# USB2BT.net
KiCad netlist of a schematic drawn in Altium Designer
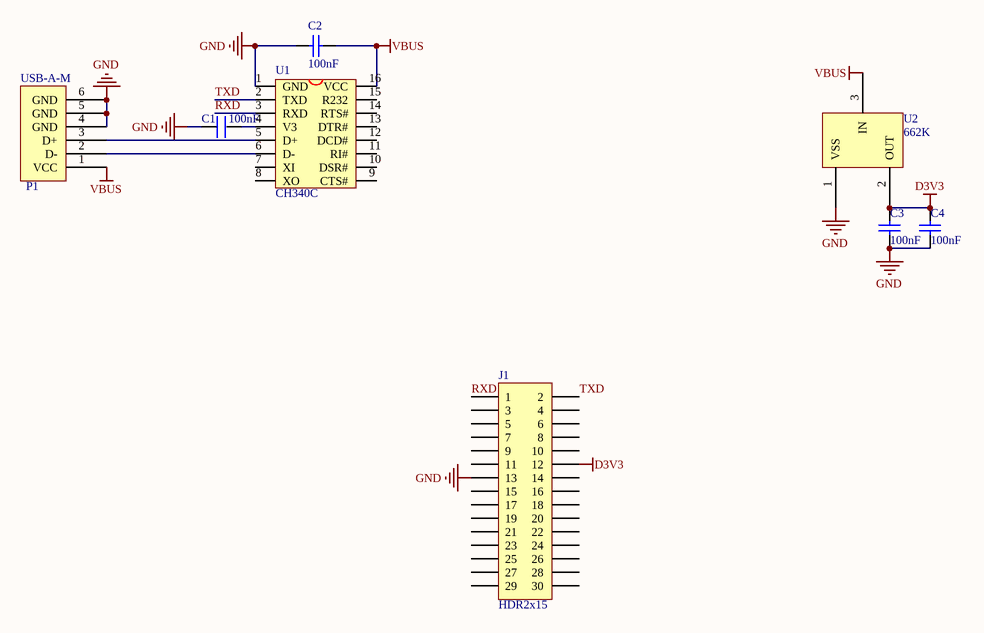
[diagram p0: USB2BT.SchDoc]

(export (version "E")
  (design (tool "Eeschema 10.0.6"))
  (components
    (comp (ref "C1")
      (value "100nF")
      (footprint "0603C")
      (libsource (lib "WarShip V3 STM32103封装库") (part "C"))
    )
    (comp (ref "C2")
      (value "100nF")
      (footprint "0603C")
      (description "Capacitor")
      (fields (field (name "PUBLISHER") "Altium Limited"))
      (libsource (lib "Crazy_PCB") (part "Cap"))
    )
    (comp (ref "C3")
      (value "100nF")
      (footprint "0603C")
      (description "Capacitor")
      (fields (field (name "PUBLISHER") "Altium Limited"))
      (libsource (lib "Crazy_PCB") (part "Cap"))
    )
    (comp (ref "C4")
      (value "100nF")
      (footprint "0603C")
      (description "Capacitor")
      (fields (field (name "PUBLISHER") "Altium Limited"))
      (libsource (lib "Crazy_PCB") (part "Cap"))
    )
    (comp (ref "J1")
      (value "HDR2x15")
      (footprint "HC-05/06/08V15")
      (description "Connector")
      (libsource (lib "General") (part "HDR2x15"))
    )
    (comp (ref "P1") (value "USB-A-M") (footprint "USB-A-M") (libsource (lib "DX") (part "USB-B")))
    (comp (ref "U1")
      (value "CH340C")
      (footprint "SO-16")
      (description "USB2UART")
      (libsource (lib "WarShip V3 STM32103封装库") (part "CH340G"))
    )
    (comp (ref "U2") (value "662K") (footprint "SOT-23") (libsource (lib "SS") (part "662K")))
  )
  (nets
    (net (code "1") (name "/RXD") (class "Default")
      (node (ref "J1") (pin "1") (pinfunction "1_1") (pintype "passive"))
      (node (ref "U1") (pin "3") (pinfunction "RXD_3") (pintype "passive"))
    )
    (net (code "2") (name "/TXD") (class "Default")
      (node (ref "J1") (pin "2") (pinfunction "2_2") (pintype "passive"))
      (node (ref "U1") (pin "2") (pinfunction "TXD_2") (pintype "passive"))
    )
    (net (code "3") (name "D3V3") (class "Default")
      (node (ref "C3") (pin "2") (pinfunction "2_2") (pintype "passive"))
      (node (ref "C4") (pin "2") (pinfunction "2_2") (pintype "passive"))
      (node (ref "J1") (pin "12") (pinfunction "12_12") (pintype "passive"))
      (node (ref "U2") (pin "2") (pinfunction "OUT_2") (pintype "passive"))
    )
    (net (code "4") (name "GND") (class "Default")
      (node (ref "C1") (pin "1") (pintype "passive"))
      (node (ref "C2") (pin "1") (pinfunction "1_1") (pintype "passive"))
      (node (ref "C3") (pin "1") (pinfunction "1_1") (pintype "passive"))
      (node (ref "C4") (pin "1") (pinfunction "1_1") (pintype "passive"))
      (node (ref "J1") (pin "13") (pinfunction "13_13") (pintype "passive"))
      (node (ref "P1") (pin "4") (pinfunction "GND_4") (pintype "passive"))
      (node (ref "P1") (pin "5") (pinfunction "GND_5") (pintype "passive"))
      (node (ref "P1") (pin "6") (pinfunction "GND_6") (pintype "passive"))
      (node (ref "U1") (pin "1") (pinfunction "GND_1") (pintype "passive"))
      (node (ref "U2") (pin "1") (pinfunction "VSS_1") (pintype "passive"))
    )
    (net (code "5") (name "Net-(P1-D+)") (class "Default")
      (node (ref "P1") (pin "3") (pinfunction "D+_3") (pintype "passive"))
      (node (ref "U1") (pin "5") (pinfunction "D+_5") (pintype "passive"))
    )
    (net (code "6") (name "Net-(P1-D-)") (class "Default")
      (node (ref "P1") (pin "2") (pinfunction "D-_2") (pintype "passive"))
      (node (ref "U1") (pin "6") (pinfunction "D-_6") (pintype "passive"))
    )
    (net (code "7") (name "Net-(U1-V3)") (class "Default")
      (node (ref "C1") (pin "2") (pintype "passive"))
      (node (ref "U1") (pin "4") (pinfunction "V3_4") (pintype "passive"))
    )
    (net (code "8") (name "VBUS") (class "Default")
      (node (ref "C2") (pin "2") (pinfunction "2_2") (pintype "passive"))
      (node (ref "P1") (pin "1") (pinfunction "VCC_1") (pintype "passive"))
      (node (ref "U1") (pin "16") (pinfunction "VCC_16") (pintype "passive"))
      (node (ref "U2") (pin "3") (pinfunction "IN_3") (pintype "passive"))
    )
    (net (code "9") (name "unconnected-(J1-Pad3)") (class "Default")
      (node (ref "J1") (pin "3") (pinfunction "3_3") (pintype "passive"))
    )
    (net (code "10") (name "unconnected-(J1-Pad4)") (class "Default")
      (node (ref "J1") (pin "4") (pinfunction "4_4") (pintype "passive"))
    )
    (net (code "11") (name "unconnected-(J1-Pad5)") (class "Default")
      (node (ref "J1") (pin "5") (pinfunction "5_5") (pintype "passive"))
    )
    (net (code "12") (name "unconnected-(J1-Pad6)") (class "Default")
      (node (ref "J1") (pin "6") (pinfunction "6_6") (pintype "passive"))
    )
    (net (code "13") (name "unconnected-(J1-Pad7)") (class "Default")
      (node (ref "J1") (pin "7") (pinfunction "7_7") (pintype "passive"))
    )
    (net (code "14") (name "unconnected-(J1-Pad8)") (class "Default")
      (node (ref "J1") (pin "8") (pinfunction "8_8") (pintype "passive"))
    )
    (net (code "15") (name "unconnected-(J1-Pad9)") (class "Default")
      (node (ref "J1") (pin "9") (pinfunction "9_9") (pintype "passive"))
    )
    (net (code "16") (name "unconnected-(J1-Pad10)") (class "Default")
      (node (ref "J1") (pin "10") (pinfunction "10_10") (pintype "passive"))
    )
    (net (code "17") (name "unconnected-(J1-Pad11)") (class "Default")
      (node (ref "J1") (pin "11") (pinfunction "11_11") (pintype "passive"))
    )
    (net (code "18") (name "unconnected-(J1-Pad14)") (class "Default")
      (node (ref "J1") (pin "14") (pinfunction "14_14") (pintype "passive"))
    )
    (net (code "19") (name "unconnected-(J1-Pad15)") (class "Default")
      (node (ref "J1") (pin "15") (pinfunction "15_15") (pintype "passive"))
    )
    (net (code "20") (name "unconnected-(J1-Pad16)") (class "Default")
      (node (ref "J1") (pin "16") (pinfunction "16_16") (pintype "passive"))
    )
    (net (code "21") (name "unconnected-(J1-Pad17)") (class "Default")
      (node (ref "J1") (pin "17") (pinfunction "17_17") (pintype "passive"))
    )
    (net (code "22") (name "unconnected-(J1-Pad18)") (class "Default")
      (node (ref "J1") (pin "18") (pinfunction "18_18") (pintype "passive"))
    )
    (net (code "23") (name "unconnected-(J1-Pad19)") (class "Default")
      (node (ref "J1") (pin "19") (pinfunction "19_19") (pintype "passive"))
    )
    (net (code "24") (name "unconnected-(J1-Pad20)") (class "Default")
      (node (ref "J1") (pin "20") (pinfunction "20_20") (pintype "passive"))
    )
    (net (code "25") (name "unconnected-(J1-Pad21)") (class "Default")
      (node (ref "J1") (pin "21") (pinfunction "21_21") (pintype "passive"))
    )
    (net (code "26") (name "unconnected-(J1-Pad22)") (class "Default")
      (node (ref "J1") (pin "22") (pinfunction "22_22") (pintype "passive"))
    )
    (net (code "27") (name "unconnected-(J1-Pad23)") (class "Default")
      (node (ref "J1") (pin "23") (pinfunction "23_23") (pintype "passive"))
    )
    (net (code "28") (name "unconnected-(J1-Pad24)") (class "Default")
      (node (ref "J1") (pin "24") (pinfunction "24_24") (pintype "passive"))
    )
    (net (code "29") (name "unconnected-(J1-Pad25)") (class "Default")
      (node (ref "J1") (pin "25") (pinfunction "25_25") (pintype "passive"))
    )
    (net (code "30") (name "unconnected-(J1-Pad26)") (class "Default")
      (node (ref "J1") (pin "26") (pinfunction "26_26") (pintype "passive"))
    )
    (net (code "31") (name "unconnected-(J1-Pad27)") (class "Default")
      (node (ref "J1") (pin "27") (pinfunction "27_27") (pintype "passive"))
    )
    (net (code "32") (name "unconnected-(J1-Pad28)") (class "Default")
      (node (ref "J1") (pin "28") (pinfunction "28_28") (pintype "passive"))
    )
    (net (code "33") (name "unconnected-(J1-Pad29)") (class "Default")
      (node (ref "J1") (pin "29") (pinfunction "29_29") (pintype "passive"))
    )
    (net (code "34") (name "unconnected-(J1-Pad30)") (class "Default")
      (node (ref "J1") (pin "30") (pinfunction "30_30") (pintype "passive"))
    )
    (net (code "35") (name "unconnected-(U1-CTS#-Pad9)") (class "Default")
      (node (ref "U1") (pin "9") (pinfunction "CTS#_9") (pintype "passive"))
    )
    (net (code "36") (name "unconnected-(U1-DCD#-Pad12)") (class "Default")
      (node (ref "U1") (pin "12") (pinfunction "DCD#_12") (pintype "passive"))
    )
    (net (code "37") (name "unconnected-(U1-DSR#-Pad10)") (class "Default")
      (node (ref "U1") (pin "10") (pinfunction "DSR#_10") (pintype "passive"))
    )
    (net (code "38") (name "unconnected-(U1-DTR#-Pad13)") (class "Default")
      (node (ref "U1") (pin "13") (pinfunction "DTR#_13") (pintype "passive"))
    )
    (net (code "39") (name "unconnected-(U1-R232-Pad15)") (class "Default")
      (node (ref "U1") (pin "15") (pinfunction "R232_15") (pintype "passive"))
    )
    (net (code "40") (name "unconnected-(U1-RI#-Pad11)") (class "Default")
      (node (ref "U1") (pin "11") (pinfunction "RI#_11") (pintype "passive"))
    )
    (net (code "41") (name "unconnected-(U1-RTS#-Pad14)") (class "Default")
      (node (ref "U1") (pin "14") (pinfunction "RTS#_14") (pintype "passive"))
    )
    (net (code "42") (name "unconnected-(U1-XI-Pad7)") (class "Default")
      (node (ref "U1") (pin "7") (pinfunction "XI_7") (pintype "passive"))
    )
    (net (code "43") (name "unconnected-(U1-XO-Pad8)") (class "Default")
      (node (ref "U1") (pin "8") (pinfunction "XO_8") (pintype "passive"))
    )
  )
)
